# 09_POWER.net
KiCad netlist of a schematic drawn in Altium Designer
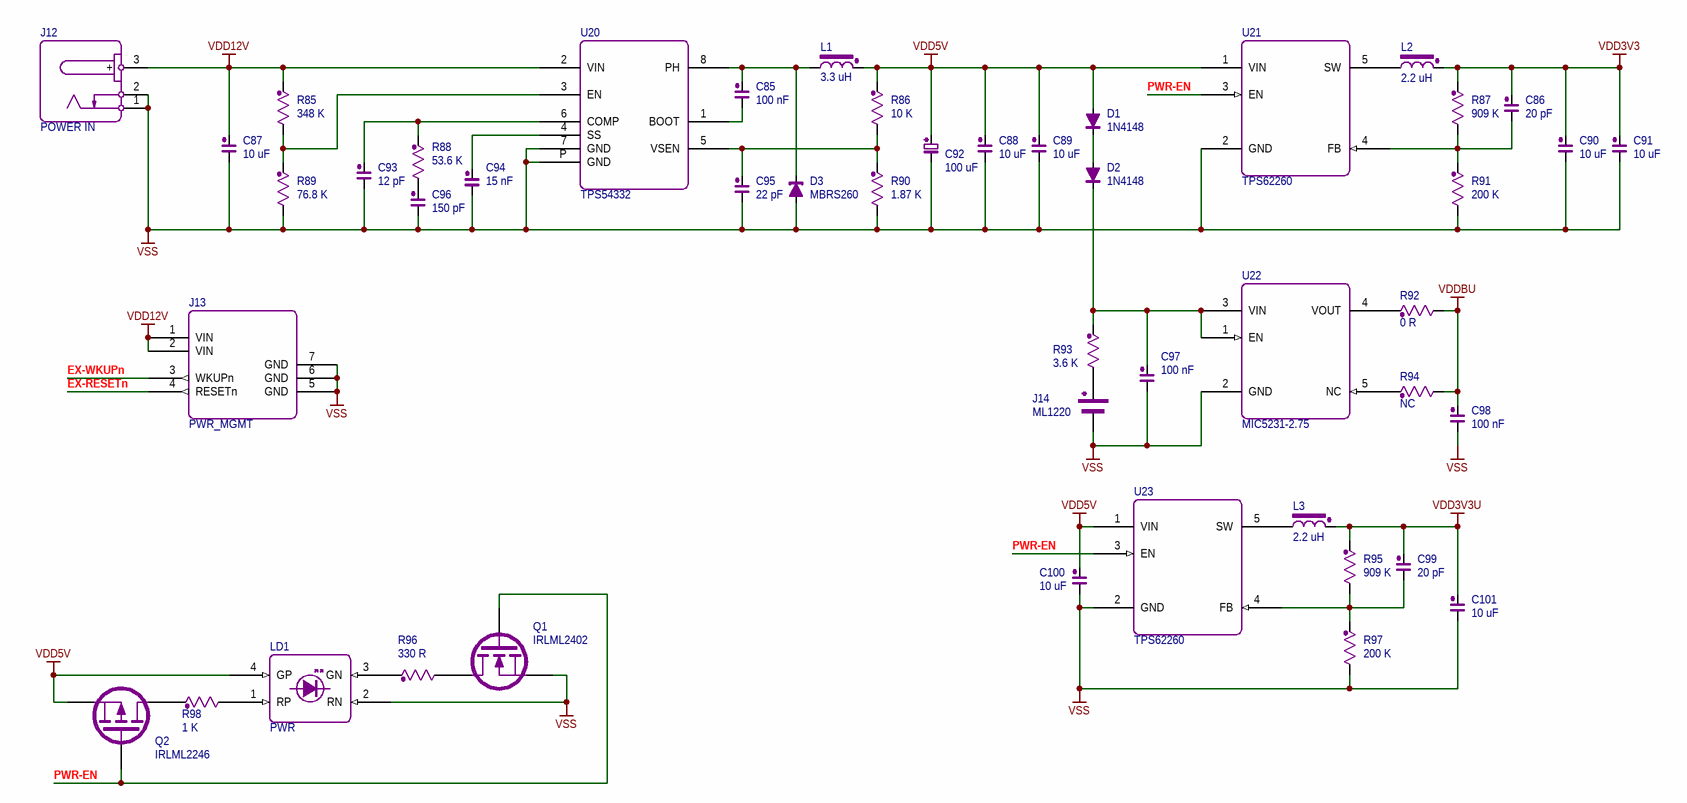
[diagram p0: 09_POWER.SchDoc]

(export (version "E")
  (design (tool "Eeschema 10.0.6"))
  (components
    (comp (ref "C85")
      (value "100 nF")
      (footprint "0603A1")
      (description "Normal Capacitor")
      (fields
        (field (name "PARTNUMBER") "0")
        (field (name "PUBLISHER") "Cowin")
        (field (name "DESIGNER") "shyul")
      )
      (libsource (lib "Basc_1_Passive") (part "CAP"))
    )
    (comp (ref "C86")
      (value "20 pF")
      (footprint "0402A1")
      (description "Normal Capacitor")
      (fields
        (field (name "PARTNUMBER") "0")
        (field (name "PUBLISHER") "Cowin")
        (field (name "DESIGNER") "shyul")
      )
      (libsource (lib "Basc_1_Passive") (part "CAP"))
    )
    (comp (ref "C87")
      (value "10 uF")
      (footprint "1210A1")
      (description "Normal Capacitor")
      (fields
        (field (name "PARTNUMBER") "0")
        (field (name "PUBLISHER") "Cowin")
        (field (name "DESIGNER") "shyul")
      )
      (libsource (lib "Basc_1_Passive") (part "CAP"))
    )
    (comp (ref "C88")
      (value "10 uF")
      (footprint "0603A1")
      (description "Normal Capacitor")
      (fields
        (field (name "PARTNUMBER") "0")
        (field (name "PUBLISHER") "Cowin")
        (field (name "DESIGNER") "shyul")
      )
      (libsource (lib "Basc_1_Passive") (part "CAP"))
    )
    (comp (ref "C89")
      (value "10 uF")
      (footprint "0603A1")
      (description "Normal Capacitor")
      (fields
        (field (name "PARTNUMBER") "0")
        (field (name "PUBLISHER") "Cowin")
        (field (name "DESIGNER") "shyul")
      )
      (libsource (lib "Basc_1_Passive") (part "CAP"))
    )
    (comp (ref "C90")
      (value "10 uF")
      (footprint "0603A1")
      (description "Normal Capacitor")
      (fields
        (field (name "PARTNUMBER") "0")
        (field (name "PUBLISHER") "Cowin")
        (field (name "DESIGNER") "shyul")
      )
      (libsource (lib "Basc_1_Passive") (part "CAP"))
    )
    (comp (ref "C91")
      (value "10 uF")
      (footprint "0603A1")
      (description "Normal Capacitor")
      (fields
        (field (name "PARTNUMBER") "0")
        (field (name "PUBLISHER") "Cowin")
        (field (name "DESIGNER") "shyul")
      )
      (libsource (lib "Basc_1_Passive") (part "CAP"))
    )
    (comp (ref "C92")
      (value "100 uF")
      (footprint "CAP_ED")
      (description "Electrolyte Capacitor")
      (fields
        (field (name "PARTNUMBER") "0")
        (field (name "DESIGNER") "shyul")
        (field (name "PUBLISHER") "Cowin")
      )
      (libsource (lib "Basc_1_Passive") (part "CAP_E"))
    )
    (comp (ref "C93")
      (value "12 pF")
      (footprint "0603A1")
      (description "Normal Capacitor")
      (fields
        (field (name "PARTNUMBER") "0")
        (field (name "PUBLISHER") "Cowin")
        (field (name "DESIGNER") "shyul")
      )
      (libsource (lib "Basc_1_Passive") (part "CAP"))
    )
    (comp (ref "C94")
      (value "15 nF")
      (footprint "0603A1")
      (description "Normal Capacitor")
      (fields
        (field (name "PARTNUMBER") "0")
        (field (name "PUBLISHER") "Cowin")
        (field (name "DESIGNER") "shyul")
      )
      (libsource (lib "Basc_1_Passive") (part "CAP"))
    )
    (comp (ref "C95")
      (value "22 pF")
      (footprint "0603A1")
      (description "Normal Capacitor")
      (fields
        (field (name "PARTNUMBER") "0")
        (field (name "PUBLISHER") "Cowin")
        (field (name "DESIGNER") "shyul")
      )
      (libsource (lib "Basc_1_Passive") (part "CAP"))
    )
    (comp (ref "C96")
      (value "150 pF")
      (footprint "0603A1")
      (description "Normal Capacitor")
      (fields
        (field (name "PARTNUMBER") "0")
        (field (name "PUBLISHER") "Cowin")
        (field (name "DESIGNER") "shyul")
      )
      (libsource (lib "Basc_1_Passive") (part "CAP"))
    )
    (comp (ref "C97")
      (value "100 nF")
      (footprint "0603A1")
      (description "Normal Capacitor")
      (fields
        (field (name "PARTNUMBER") "0")
        (field (name "PUBLISHER") "Cowin")
        (field (name "DESIGNER") "shyul")
      )
      (libsource (lib "Basc_1_Passive") (part "CAP"))
    )
    (comp (ref "C98")
      (value "100 nF")
      (footprint "0603A1")
      (description "Normal Capacitor")
      (fields
        (field (name "PARTNUMBER") "0")
        (field (name "PUBLISHER") "Cowin")
        (field (name "DESIGNER") "shyul")
      )
      (libsource (lib "Basc_1_Passive") (part "CAP"))
    )
    (comp (ref "C99")
      (value "20 pF")
      (footprint "0402A1")
      (description "Normal Capacitor")
      (fields
        (field (name "PARTNUMBER") "0")
        (field (name "PUBLISHER") "Cowin")
        (field (name "DESIGNER") "shyul")
      )
      (libsource (lib "Basc_1_Passive") (part "CAP"))
    )
    (comp (ref "C100")
      (value "10 uF")
      (footprint "0603A1")
      (description "Normal Capacitor")
      (fields
        (field (name "PARTNUMBER") "0")
        (field (name "PUBLISHER") "Cowin")
        (field (name "DESIGNER") "shyul")
      )
      (libsource (lib "Basc_1_Passive") (part "CAP"))
    )
    (comp (ref "C101")
      (value "10 uF")
      (footprint "0603A1")
      (description "Normal Capacitor")
      (fields
        (field (name "PARTNUMBER") "0")
        (field (name "PUBLISHER") "Cowin")
        (field (name "DESIGNER") "shyul")
      )
      (libsource (lib "Basc_1_Passive") (part "CAP"))
    )
    (comp (ref "D1")
      (value "1N4148")
      (footprint "SOD-123")
      (description "Normal Diode")
      (fields
        (field (name "PARTNUMBER") "0")
        (field (name "DESIGNER") "shyul")
        (field (name "PUBLISHER") "Cowin")
      )
      (libsource (lib "Basc_3_Diode_Transistor") (part "DIODE"))
    )
    (comp (ref "D2")
      (value "1N4148")
      (footprint "SOD-123")
      (description "Normal Diode")
      (fields
        (field (name "PARTNUMBER") "0")
        (field (name "DESIGNER") "shyul")
        (field (name "PUBLISHER") "Cowin")
      )
      (libsource (lib "Basc_3_Diode_Transistor") (part "DIODE"))
    )
    (comp (ref "D3")
      (value "MBRS260")
      (footprint "D-SMB")
      (description "Schottky Diode")
      (fields
        (field (name "PARTNUMBER") "0")
        (field (name "DESIGNER") "shyul")
        (field (name "PUBLISHER") "Cowin")
      )
      (libsource (lib "Basc_3_Diode_Transistor") (part "DIODE_S"))
    )
    (comp (ref "J12")
      (value "POWER IN")
      (footprint "PWRIN_JACK_1")
      (description "Standard Power Input Type 1")
      (libsource (lib "Connector_1_General") (part "PWRIN_JACK_1"))
    )
    (comp (ref "J13")
      (value "PWR_MGMT")
      (footprint "PWR_MGMT")
      (description "Lophilo Power Management")
      (fields (field (name "PUBLISHER") "Cowin") (field (name "DESIGNER") "shyul"))
      (libsource (lib "PCB_MDB-U01") (part "PWR_MGMT"))
    )
    (comp (ref "J14")
      (value "ML1220")
      (footprint "BAT_SCKT_1220")
      (description "Battery")
      (fields
        (field (name "PARTNUMBER") "SOCKET_1220")
        (field (name "PUBLISHER") "Cowin")
        (field (name "DESIGNER") "shyul")
      )
      (libsource (lib "Connector_6_Battery") (part "BAT_A"))
    )
    (comp (ref "L1")
      (value "3.3 uH")
      (footprint "COIL_S_7X7")
      (description "Power Coil Inductor")
      (fields
        (field (name "PARTNUMBER") "MPLCH0740L3R3(SA)")
        (field (name "PUBLISHER") "Cowin")
        (field (name "DESIGNER") "shyul")
      )
      (libsource (lib "Basc_1_Passive") (part "COIL"))
    )
    (comp (ref "L2")
      (value "2.2 uH")
      (footprint "COIL_S_3X3")
      (description "Power Coil Inductor")
      (fields
        (field (name "PARTNUMBER") "LPS3010-222MLB")
        (field (name "PUBLISHER") "Cowin")
        (field (name "DESIGNER") "shyul")
      )
      (libsource (lib "Basc_1_Passive") (part "COIL"))
    )
    (comp (ref "L3")
      (value "2.2 uH")
      (footprint "COIL_S_3X3")
      (description "Power Coil Inductor")
      (fields
        (field (name "PARTNUMBER") "LPS3010-222MLB")
        (field (name "PUBLISHER") "Cowin")
        (field (name "DESIGNER") "shyul")
      )
      (libsource (lib "Basc_1_Passive") (part "COIL"))
    )
    (comp (ref "LD1")
      (value "PWR")
      (footprint "LED_4A_S_S195")
      (description "LED Pack 2")
      (fields
        (field (name "PARTNUMBER") "LL-S195VUGC-2B")
        (field (name "DESIGNER") "shyul")
        (field (name "PUBLISHER") "Cowin")
      )
      (libsource (lib "Basc_4_Other") (part "LED_2A"))
    )
    (comp (ref "Q1")
      (value "IRLML2402")
      (footprint "SOT-23-3")
      (description "N Channel Enhancement MOSFET")
      (fields
        (field (name "PARTNUMBER") "0")
        (field (name "PUBLISHER") "Cowin")
        (field (name "DESIGNER") "shyul")
      )
      (libsource (lib "Basc_3_Diode_Transistor") (part "MOSFET_EN"))
    )
    (comp (ref "Q2")
      (value "IRLML2246")
      (footprint "SOT-23-3")
      (description "P Channel Enhancement MOSFET")
      (fields
        (field (name "PARTNUMBER") "IRLML2246TRPbF")
        (field (name "PUBLISHER") "Cowin")
        (field (name "DESIGNER") "shyul")
      )
      (libsource (lib "Basc_3_Diode_Transistor") (part "MOSFET_EP"))
    )
    (comp (ref "R85")
      (value "348 K")
      (footprint "0603A2")
      (description "Normal Resistor")
      (fields
        (field (name "PARTNUMBER") "0")
        (field (name "DESIGNER") "shyul")
        (field (name "PUBLISHER") "Cowin")
      )
      (libsource (lib "Basc_1_Passive") (part "RES"))
    )
    (comp (ref "R86")
      (value "10 K")
      (footprint "0603A2")
      (description "Normal Resistor")
      (fields
        (field (name "PARTNUMBER") "0")
        (field (name "DESIGNER") "shyul")
        (field (name "PUBLISHER") "Cowin")
      )
      (libsource (lib "Basc_1_Passive") (part "RES"))
    )
    (comp (ref "R87")
      (value "909 K")
      (footprint "0402A2")
      (description "Normal Resistor")
      (fields
        (field (name "PARTNUMBER") "0")
        (field (name "DESIGNER") "shyul")
        (field (name "PUBLISHER") "Cowin")
      )
      (libsource (lib "Basc_1_Passive") (part "RES"))
    )
    (comp (ref "R88")
      (value "53.6 K")
      (footprint "0603A2")
      (description "Normal Resistor")
      (fields
        (field (name "PARTNUMBER") "0")
        (field (name "DESIGNER") "shyul")
        (field (name "PUBLISHER") "Cowin")
      )
      (libsource (lib "Basc_1_Passive") (part "RES"))
    )
    (comp (ref "R89")
      (value "76.8 K")
      (footprint "0603A2")
      (description "Normal Resistor")
      (fields
        (field (name "PARTNUMBER") "0")
        (field (name "DESIGNER") "shyul")
        (field (name "PUBLISHER") "Cowin")
      )
      (libsource (lib "Basc_1_Passive") (part "RES"))
    )
    (comp (ref "R90")
      (value "1.87 K")
      (footprint "0603A2")
      (description "Normal Resistor")
      (fields
        (field (name "PARTNUMBER") "0")
        (field (name "DESIGNER") "shyul")
        (field (name "PUBLISHER") "Cowin")
      )
      (libsource (lib "Basc_1_Passive") (part "RES"))
    )
    (comp (ref "R91")
      (value "200 K")
      (footprint "0402A2")
      (description "Normal Resistor")
      (fields
        (field (name "PARTNUMBER") "0")
        (field (name "DESIGNER") "shyul")
        (field (name "PUBLISHER") "Cowin")
      )
      (libsource (lib "Basc_1_Passive") (part "RES"))
    )
    (comp (ref "R92")
      (value "0 R")
      (footprint "0402A2")
      (description "Normal Resistor")
      (fields
        (field (name "PARTNUMBER") "0")
        (field (name "DESIGNER") "shyul")
        (field (name "PUBLISHER") "Cowin")
      )
      (libsource (lib "Basc_1_Passive") (part "RES"))
    )
    (comp (ref "R93")
      (value "3.6 K")
      (footprint "0603A2")
      (description "Normal Resistor")
      (fields
        (field (name "PARTNUMBER") "0")
        (field (name "DESIGNER") "shyul")
        (field (name "PUBLISHER") "Cowin")
      )
      (libsource (lib "Basc_1_Passive") (part "RES"))
    )
    (comp (ref "R94")
      (value "NC")
      (footprint "0402A2")
      (description "Normal Resistor")
      (fields
        (field (name "PARTNUMBER") "0")
        (field (name "DESIGNER") "shyul")
        (field (name "PUBLISHER") "Cowin")
      )
      (libsource (lib "Basc_1_Passive") (part "RES"))
    )
    (comp (ref "R95")
      (value "909 K")
      (footprint "0402A2")
      (description "Normal Resistor")
      (fields
        (field (name "PARTNUMBER") "0")
        (field (name "DESIGNER") "shyul")
        (field (name "PUBLISHER") "Cowin")
      )
      (libsource (lib "Basc_1_Passive") (part "RES"))
    )
    (comp (ref "R96")
      (value "330 R")
      (footprint "0402A2")
      (description "Normal Resistor")
      (fields
        (field (name "PARTNUMBER") "0")
        (field (name "DESIGNER") "shyul")
        (field (name "PUBLISHER") "Cowin")
      )
      (libsource (lib "Basc_1_Passive") (part "RES"))
    )
    (comp (ref "R97")
      (value "200 K")
      (footprint "0402A2")
      (description "Normal Resistor")
      (fields
        (field (name "PARTNUMBER") "0")
        (field (name "DESIGNER") "shyul")
        (field (name "PUBLISHER") "Cowin")
      )
      (libsource (lib "Basc_1_Passive") (part "RES"))
    )
    (comp (ref "R98")
      (value "1 K")
      (footprint "0402A2")
      (description "Normal Resistor")
      (fields
        (field (name "PARTNUMBER") "0")
        (field (name "DESIGNER") "shyul")
        (field (name "PUBLISHER") "Cowin")
      )
      (libsource (lib "Basc_1_Passive") (part "RES"))
    )
    (comp (ref "U20")
      (value "TPS54332")
      (footprint "SOIC-8SE")
      (description "TI Simple Switch Adjustable 3A")
      (fields
        (field (name "PARTNUMBER") "TPS54332DDAR")
        (field (name "PUBLISHER") "Cowin")
        (field (name "DESIGNER") "shyul")
      )
      (libsource (lib "IC_10_Regulator") (part "TPS54332"))
    )
    (comp (ref "U21")
      (value "TPS62260")
      (footprint "SOT-23-5")
      (description "Simple Switch 600mA Adjustable")
      (fields
        (field (name "PARTNUMBER") "TPS62260DDCR")
        (field (name "PUBLISHER") "Cowin")
        (field (name "DESIGNER") "shyul")
      )
      (libsource (lib "PCB_XEM-S91") (part "TPS62260"))
    )
    (comp (ref "U22")
      (value "MIC5231-2.75")
      (footprint "SOT-23-5")
      (description "LDO Micro")
      (fields
        (field (name "PARTNUMBER") "MIC5231-2.75YM5")
        (field (name "PUBLISHER") "Cowin")
        (field (name "DESIGNER") "shyul")
      )
      (libsource (lib "IC_10_Regulator") (part "MIC5231"))
    )
    (comp (ref "U23")
      (value "TPS62260")
      (footprint "SOT-23-5")
      (description "Simple Switch 600mA Adjustable")
      (fields
        (field (name "PARTNUMBER") "TPS62260DDCR")
        (field (name "PUBLISHER") "Cowin")
        (field (name "DESIGNER") "shyul")
      )
      (libsource (lib "PCB_XEM-S91") (part "TPS62260"))
    )
  )
  (nets
    (net (code "1") (name "/EX-RESETn") (class "Default")
      (node (ref "J13") (pin "4") (pinfunction "RESETn_4") (pintype "output"))
    )
    (net (code "2") (name "/EX-WKUPn") (class "Default")
      (node (ref "J13") (pin "3") (pinfunction "WKUPn_3") (pintype "output"))
    )
    (net (code "3") (name "/PWR-EN") (class "Default")
      (node (ref "Q1") (pin "1") (pinfunction "G_1") (pintype "passive"))
      (node (ref "Q2") (pin "1") (pinfunction "G_1") (pintype "passive"))
      (node (ref "U21") (pin "3") (pinfunction "EN_3") (pintype "input"))
      (node (ref "U23") (pin "3") (pinfunction "EN_3") (pintype "input"))
    )
    (net (code "4") (name "Net-(C96-Pad2)") (class "Default")
      (node (ref "C96") (pin "2") (pinfunction "2_2") (pintype "passive"))
      (node (ref "R88") (pin "1") (pinfunction "1_1") (pintype "passive"))
    )
    (net (code "5") (name "Net-(D1-Pad1)") (class "Default")
      (node (ref "D1") (pin "1") (pinfunction "1_1") (pintype "passive"))
      (node (ref "D2") (pin "2") (pinfunction "2_2") (pintype "passive"))
    )
    (net (code "6") (name "Net-(J14-Pad2)") (class "Default")
      (node (ref "J14") (pin "2") (pinfunction "2_2") (pintype "power_in"))
      (node (ref "R93") (pin "1") (pinfunction "1_1") (pintype "passive"))
    )
    (net (code "7") (name "Net-(LD1-GN)") (class "Default")
      (node (ref "LD1") (pin "3") (pinfunction "GN_3") (pintype "input"))
      (node (ref "R96") (pin "2") (pinfunction "2_2") (pintype "passive"))
    )
    (net (code "8") (name "Net-(LD1-RP)") (class "Default")
      (node (ref "LD1") (pin "1") (pinfunction "RP_1") (pintype "input"))
      (node (ref "R98") (pin "1") (pinfunction "1_1") (pintype "passive"))
    )
    (net (code "9") (name "Net-(Q1-D)") (class "Default")
      (node (ref "Q1") (pin "2") (pinfunction "D_2") (pintype "passive"))
      (node (ref "R96") (pin "1") (pinfunction "1_1") (pintype "passive"))
    )
    (net (code "10") (name "Net-(Q2-D)") (class "Default")
      (node (ref "Q2") (pin "2") (pinfunction "D_2") (pintype "passive"))
      (node (ref "R98") (pin "2") (pinfunction "2_2") (pintype "passive"))
    )
    (net (code "11") (name "Net-(U20-BOOT)") (class "Default")
      (node (ref "C85") (pin "1") (pinfunction "1_1") (pintype "passive"))
      (node (ref "U20") (pin "1") (pinfunction "BOOT_1") (pintype "passive"))
    )
    (net (code "12") (name "Net-(U20-COMP)") (class "Default")
      (node (ref "C93") (pin "2") (pinfunction "2_2") (pintype "passive"))
      (node (ref "R88") (pin "2") (pinfunction "2_2") (pintype "passive"))
      (node (ref "U20") (pin "6") (pinfunction "COMP_6") (pintype "passive"))
    )
    (net (code "13") (name "Net-(U20-EN)") (class "Default")
      (node (ref "R85") (pin "1") (pinfunction "1_1") (pintype "passive"))
      (node (ref "R89") (pin "2") (pinfunction "2_2") (pintype "passive"))
      (node (ref "U20") (pin "3") (pinfunction "EN_3") (pintype "passive"))
    )
    (net (code "14") (name "Net-(U20-PH)") (class "Default")
      (node (ref "C85") (pin "2") (pinfunction "2_2") (pintype "passive"))
      (node (ref "D3") (pin "1") (pinfunction "1_1") (pintype "passive"))
      (node (ref "L1") (pin "1") (pinfunction "1_1") (pintype "passive"))
      (node (ref "U20") (pin "8") (pinfunction "PH_8") (pintype "passive"))
    )
    (net (code "15") (name "Net-(U20-SS)") (class "Default")
      (node (ref "C94") (pin "2") (pinfunction "2_2") (pintype "passive"))
      (node (ref "U20") (pin "4") (pinfunction "SS_4") (pintype "passive"))
    )
    (net (code "16") (name "Net-(U20-VSEN)") (class "Default")
      (node (ref "C95") (pin "2") (pinfunction "2_2") (pintype "passive"))
      (node (ref "R86") (pin "1") (pinfunction "1_1") (pintype "passive"))
      (node (ref "R90") (pin "2") (pinfunction "2_2") (pintype "passive"))
      (node (ref "U20") (pin "5") (pinfunction "VSEN_5") (pintype "passive"))
    )
    (net (code "17") (name "Net-(U21-FB)") (class "Default")
      (node (ref "C86") (pin "1") (pinfunction "1_1") (pintype "passive"))
      (node (ref "R87") (pin "1") (pinfunction "1_1") (pintype "passive"))
      (node (ref "R91") (pin "2") (pinfunction "2_2") (pintype "passive"))
      (node (ref "U21") (pin "4") (pinfunction "FB_4") (pintype "input"))
    )
    (net (code "18") (name "Net-(U21-SW)") (class "Default")
      (node (ref "L2") (pin "1") (pinfunction "1_1") (pintype "passive"))
      (node (ref "U21") (pin "5") (pinfunction "SW_5") (pintype "power_in"))
    )
    (net (code "19") (name "Net-(U22-EN)") (class "Default")
      (node (ref "C97") (pin "2") (pinfunction "2_2") (pintype "passive"))
      (node (ref "D2") (pin "1") (pinfunction "1_1") (pintype "passive"))
      (node (ref "R93") (pin "2") (pinfunction "2_2") (pintype "passive"))
      (node (ref "U22") (pin "1") (pinfunction "EN_1") (pintype "input"))
      (node (ref "U22") (pin "3") (pinfunction "VIN_3") (pintype "power_in"))
    )
    (net (code "20") (name "Net-(U22-NC)") (class "Default")
      (node (ref "R94") (pin "2") (pinfunction "2_2") (pintype "passive"))
      (node (ref "U22") (pin "5") (pinfunction "NC_5") (pintype "input"))
    )
    (net (code "21") (name "Net-(U22-VOUT)") (class "Default")
      (node (ref "R92") (pin "2") (pinfunction "2_2") (pintype "passive"))
      (node (ref "U22") (pin "4") (pinfunction "VOUT_4") (pintype "power_in"))
    )
    (net (code "22") (name "Net-(U23-FB)") (class "Default")
      (node (ref "C99") (pin "1") (pinfunction "1_1") (pintype "passive"))
      (node (ref "R95") (pin "1") (pinfunction "1_1") (pintype "passive"))
      (node (ref "R97") (pin "2") (pinfunction "2_2") (pintype "passive"))
      (node (ref "U23") (pin "4") (pinfunction "FB_4") (pintype "input"))
    )
    (net (code "23") (name "Net-(U23-SW)") (class "Default")
      (node (ref "L3") (pin "1") (pinfunction "1_1") (pintype "passive"))
      (node (ref "U23") (pin "5") (pinfunction "SW_5") (pintype "power_in"))
    )
    (net (code "24") (name "VDD3V3") (class "Default")
      (node (ref "C86") (pin "2") (pinfunction "2_2") (pintype "passive"))
      (node (ref "C90") (pin "2") (pinfunction "2_2") (pintype "passive"))
      (node (ref "C91") (pin "2") (pinfunction "2_2") (pintype "passive"))
      (node (ref "L2") (pin "2") (pinfunction "2_2") (pintype "passive"))
      (node (ref "R87") (pin "2") (pinfunction "2_2") (pintype "passive"))
    )
    (net (code "25") (name "VDD3V3U") (class "Default")
      (node (ref "C101") (pin "2") (pinfunction "2_2") (pintype "passive"))
      (node (ref "C99") (pin "2") (pinfunction "2_2") (pintype "passive"))
      (node (ref "L3") (pin "2") (pinfunction "2_2") (pintype "passive"))
      (node (ref "R95") (pin "2") (pinfunction "2_2") (pintype "passive"))
    )
    (net (code "26") (name "VDD5V") (class "Default")
      (node (ref "C100") (pin "2") (pinfunction "2_2") (pintype "passive"))
      (node (ref "C88") (pin "2") (pinfunction "2_2") (pintype "passive"))
      (node (ref "C89") (pin "2") (pinfunction "2_2") (pintype "passive"))
      (node (ref "C92") (pin "2") (pinfunction "2_2") (pintype "passive"))
      (node (ref "D1") (pin "2") (pinfunction "2_2") (pintype "passive"))
      (node (ref "L1") (pin "2") (pinfunction "2_2") (pintype "passive"))
      (node (ref "LD1") (pin "4") (pinfunction "GP_4") (pintype "input"))
      (node (ref "Q2") (pin "3") (pinfunction "S_3") (pintype "passive"))
      (node (ref "R86") (pin "2") (pinfunction "2_2") (pintype "passive"))
      (node (ref "U21") (pin "1") (pinfunction "VIN_1") (pintype "passive"))
      (node (ref "U23") (pin "1") (pinfunction "VIN_1") (pintype "passive"))
    )
    (net (code "27") (name "VDD12V") (class "Default")
      (node (ref "C87") (pin "2") (pinfunction "2_2") (pintype "passive"))
      (node (ref "J12") (pin "3") (pinfunction "+_3") (pintype "passive"))
      (node (ref "J13") (pin "1") (pinfunction "VIN_1") (pintype "power_in"))
      (node (ref "J13") (pin "2") (pinfunction "VIN_2") (pintype "power_in"))
      (node (ref "R85") (pin "2") (pinfunction "2_2") (pintype "passive"))
      (node (ref "U20") (pin "2") (pinfunction "VIN_2") (pintype "passive"))
    )
    (net (code "28") (name "VDDBU") (class "Default")
      (node (ref "C98") (pin "2") (pinfunction "2_2") (pintype "passive"))
      (node (ref "R92") (pin "1") (pinfunction "1_1") (pintype "passive"))
      (node (ref "R94") (pin "1") (pinfunction "1_1") (pintype "passive"))
    )
    (net (code "29") (name "VSS") (class "Default")
      (node (ref "C100") (pin "1") (pinfunction "1_1") (pintype "passive"))
      (node (ref "C101") (pin "1") (pinfunction "1_1") (pintype "passive"))
      (node (ref "C87") (pin "1") (pinfunction "1_1") (pintype "passive"))
      (node (ref "C88") (pin "1") (pinfunction "1_1") (pintype "passive"))
      (node (ref "C89") (pin "1") (pinfunction "1_1") (pintype "passive"))
      (node (ref "C90") (pin "1") (pinfunction "1_1") (pintype "passive"))
      (node (ref "C91") (pin "1") (pinfunction "1_1") (pintype "passive"))
      (node (ref "C92") (pin "1") (pinfunction "1_1") (pintype "passive"))
      (node (ref "C93") (pin "1") (pinfunction "1_1") (pintype "passive"))
      (node (ref "C94") (pin "1") (pinfunction "1_1") (pintype "passive"))
      (node (ref "C95") (pin "1") (pinfunction "1_1") (pintype "passive"))
      (node (ref "C96") (pin "1") (pinfunction "1_1") (pintype "passive"))
      (node (ref "C97") (pin "1") (pinfunction "1_1") (pintype "passive"))
      (node (ref "C98") (pin "1") (pinfunction "1_1") (pintype "passive"))
      (node (ref "D3") (pin "2") (pinfunction "2_2") (pintype "passive"))
      (node (ref "J12") (pin "1") (pinfunction "-_1") (pintype "passive"))
      (node (ref "J12") (pin "2") (pinfunction "J_2") (pintype "passive"))
      (node (ref "J13") (pin "5") (pinfunction "GND_5") (pintype "passive"))
      (node (ref "J13") (pin "6") (pinfunction "GND_6") (pintype "passive"))
      (node (ref "J13") (pin "7") (pinfunction "GND_7") (pintype "passive"))
      (node (ref "J14") (pin "1") (pinfunction "1_1") (pintype "power_in"))
      (node (ref "LD1") (pin "2") (pinfunction "RN_2") (pintype "input"))
      (node (ref "Q1") (pin "3") (pinfunction "S_3") (pintype "passive"))
      (node (ref "R89") (pin "1") (pinfunction "1_1") (pintype "passive"))
      (node (ref "R90") (pin "1") (pinfunction "1_1") (pintype "passive"))
      (node (ref "R91") (pin "1") (pinfunction "1_1") (pintype "passive"))
      (node (ref "R97") (pin "1") (pinfunction "1_1") (pintype "passive"))
      (node (ref "U20") (pin "7") (pinfunction "GND_7") (pintype "passive"))
      (node (ref "U20") (pin "P") (pinfunction "GND_P") (pintype "power_in"))
      (node (ref "U21") (pin "2") (pinfunction "GND_2") (pintype "passive"))
      (node (ref "U22") (pin "2") (pinfunction "GND_2") (pintype "power_in"))
      (node (ref "U23") (pin "2") (pinfunction "GND_2") (pintype "passive"))
    )
  )
)
